# FPGA.net
KiCad netlist of a schematic drawn in Altium Designer
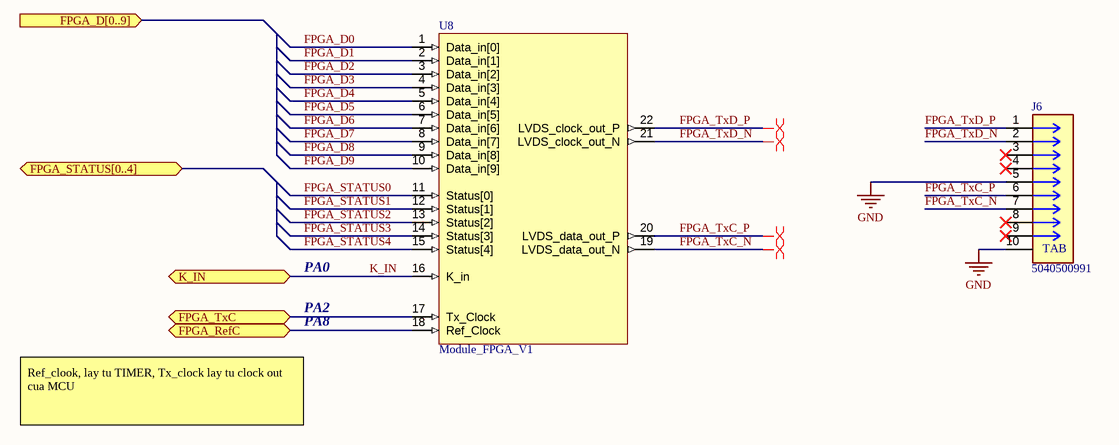
[diagram p0: FPGA.SchDoc]

(export (version "E")
  (design (tool "Eeschema 10.0.6"))
  (components
    (comp (ref "J6")
      (value "5040500991")
      (footprint "5040500991")
      (description "Connector Header Surface Mount, Right Angle 9 position 0.059\" (1.50mm)")
      (libsource (lib "COMM_SCHLIB") (part "5040500991"))
    )
    (comp (ref "U8")
      (value "Module_FPGA_V1")
      (footprint "MODULE_FPGA")
      (libsource (lib "3_HuyHung") (part "Module_FPGA_V1"))
    )
  )
  (nets
    (net (code "1") (name "/FPGA_D0") (class "Default")
      (node (ref "U8") (pin "1") (pinfunction "Data_in[0]_1") (pintype "input"))
    )
    (net (code "2") (name "/FPGA_D1") (class "Default")
      (node (ref "U8") (pin "2") (pinfunction "Data_in[1]_2") (pintype "input"))
    )
    (net (code "3") (name "/FPGA_D2") (class "Default")
      (node (ref "U8") (pin "3") (pinfunction "Data_in[2]_3") (pintype "input"))
    )
    (net (code "4") (name "/FPGA_D3") (class "Default")
      (node (ref "U8") (pin "4") (pinfunction "Data_in[3]_4") (pintype "input"))
    )
    (net (code "5") (name "/FPGA_D4") (class "Default")
      (node (ref "U8") (pin "5") (pinfunction "Data_in[4]_5") (pintype "input"))
    )
    (net (code "6") (name "/FPGA_D5") (class "Default")
      (node (ref "U8") (pin "6") (pinfunction "Data_in[5]_6") (pintype "input"))
    )
    (net (code "7") (name "/FPGA_D6") (class "Default")
      (node (ref "U8") (pin "7") (pinfunction "Data_in[6]_7") (pintype "input"))
    )
    (net (code "8") (name "/FPGA_D7") (class "Default")
      (node (ref "U8") (pin "8") (pinfunction "Data_in[7]_8") (pintype "input"))
    )
    (net (code "9") (name "/FPGA_D8") (class "Default")
      (node (ref "U8") (pin "9") (pinfunction "Data_in[8]_9") (pintype "input"))
    )
    (net (code "10") (name "/FPGA_D9") (class "Default")
      (node (ref "U8") (pin "10") (pinfunction "Data_in[9]_10") (pintype "input"))
    )
    (net (code "12") (name "/FPGA_RefC") (class "Default")
      (node (ref "U8") (pin "18") (pinfunction "Ref_Clock_18") (pintype "input"))
    )
    (net (code "13") (name "/FPGA_STATUS0") (class "Default")
      (node (ref "U8") (pin "11") (pinfunction "Status[0]_11") (pintype "input"))
    )
    (net (code "14") (name "/FPGA_STATUS1") (class "Default")
      (node (ref "U8") (pin "12") (pinfunction "Status[1]_12") (pintype "input"))
    )
    (net (code "15") (name "/FPGA_STATUS2") (class "Default")
      (node (ref "U8") (pin "13") (pinfunction "Status[2]_13") (pintype "input"))
    )
    (net (code "16") (name "/FPGA_STATUS3") (class "Default")
      (node (ref "U8") (pin "14") (pinfunction "Status[3]_14") (pintype "input"))
    )
    (net (code "17") (name "/FPGA_STATUS4") (class "Default")
      (node (ref "U8") (pin "15") (pinfunction "Status[4]_15") (pintype "input"))
    )
    (net (code "19") (name "/FPGA_TxC") (class "Default")
      (node (ref "U8") (pin "17") (pinfunction "Tx_Clock_17") (pintype "input"))
    )
    (net (code "20") (name "/FPGA_TxC_N") (class "Default")
      (node (ref "J6") (pin "7") (pinfunction "7_7") (pintype "passive"))
      (node (ref "U8") (pin "19") (pinfunction "LVDS_data_out_N_19") (pintype "output"))
    )
    (net (code "21") (name "/FPGA_TxC_P") (class "Default")
      (node (ref "J6") (pin "6") (pinfunction "6_6") (pintype "passive"))
      (node (ref "U8") (pin "20") (pinfunction "LVDS_data_out_P_20") (pintype "output"))
    )
    (net (code "22") (name "/FPGA_TxD_N") (class "Default")
      (node (ref "J6") (pin "2") (pinfunction "2_2") (pintype "passive"))
      (node (ref "U8") (pin "21") (pinfunction "LVDS_clock_out_N_21") (pintype "output"))
    )
    (net (code "23") (name "/FPGA_TxD_P") (class "Default")
      (node (ref "J6") (pin "1") (pinfunction "1_1") (pintype "passive"))
      (node (ref "U8") (pin "22") (pinfunction "LVDS_clock_out_P_22") (pintype "output"))
    )
    (net (code "24") (name "/K_IN") (class "Default")
      (node (ref "U8") (pin "16") (pinfunction "K_in_16") (pintype "input"))
    )
    (net (code "25") (name "GND") (class "Default")
      (node (ref "J6") (pin "10") (pinfunction "10_10") (pintype "passive"))
      (node (ref "J6") (pin "5") (pinfunction "5_5") (pintype "passive"))
    )
    (net (code "26") (name "unconnected-(J6-Pad3)") (class "Default")
      (node (ref "J6") (pin "3") (pinfunction "3_3") (pintype "passive+no_connect"))
    )
    (net (code "27") (name "unconnected-(J6-Pad4)") (class "Default")
      (node (ref "J6") (pin "4") (pinfunction "4_4") (pintype "passive+no_connect"))
    )
    (net (code "28") (name "unconnected-(J6-Pad8)") (class "Default")
      (node (ref "J6") (pin "8") (pinfunction "8_8") (pintype "passive+no_connect"))
    )
    (net (code "29") (name "unconnected-(J6-Pad9)") (class "Default")
      (node (ref "J6") (pin "9") (pinfunction "9_9") (pintype "passive+no_connect"))
    )
  )
)
